# d1-stepper-shield.net
KiCad netlist of a schematic drawn in EAGLE
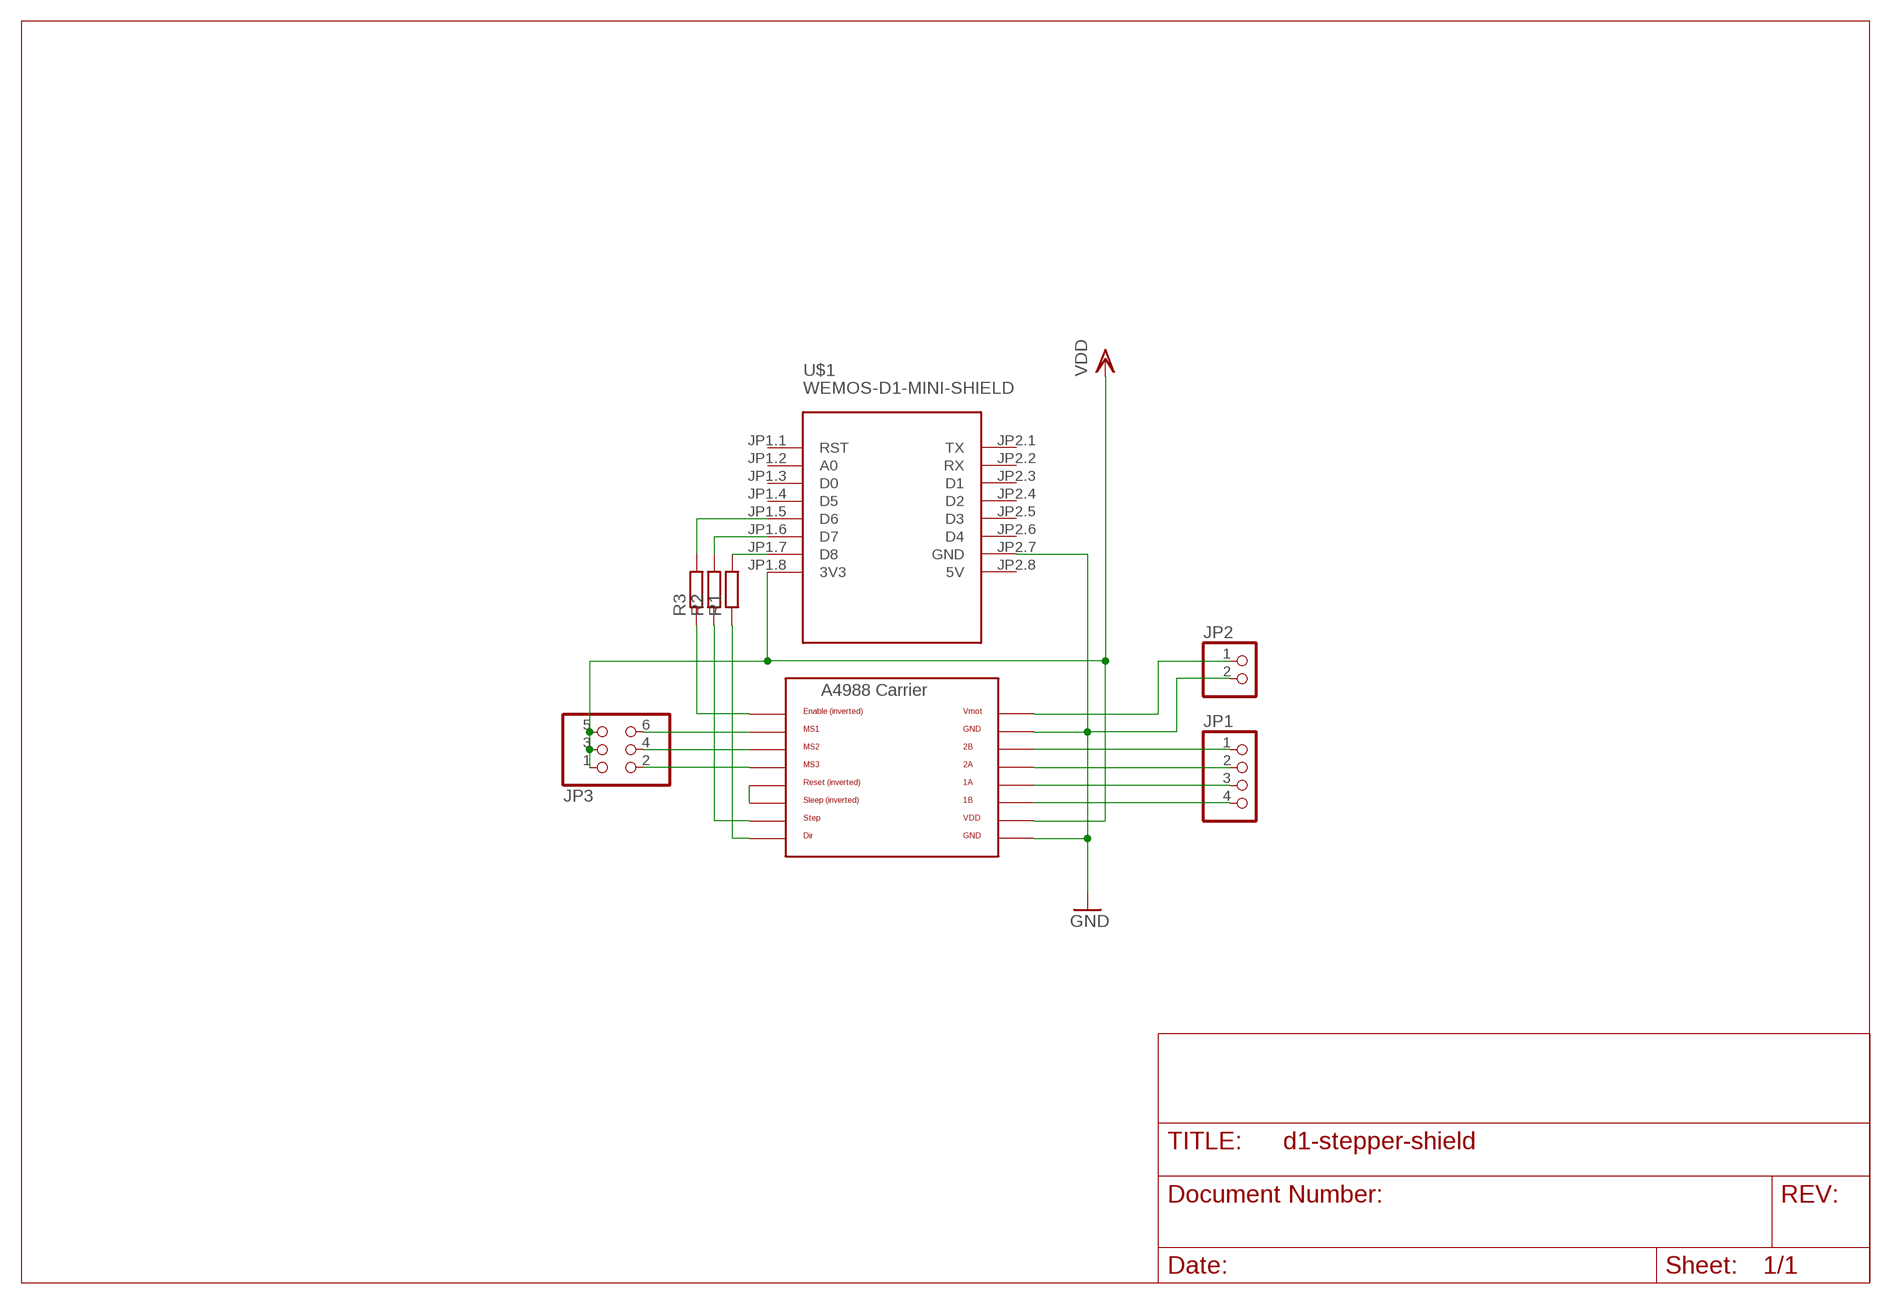
[diagram p0: schematic, sheet 1]

(export (version "E")
  (design (tool "Eeschema 10.0.6"))
  (components
    (comp (ref "JP1")
      (value "PINHD-1X4")
      (footprint "eagle-import:1X04")
      (libsource (lib "eagle-import") (part "PINHD-1X4"))
    )
    (comp (ref "JP2")
      (value "PINHD-1X2")
      (footprint "eagle-import:1X02")
      (libsource (lib "eagle-import") (part "PINHD-1X2"))
    )
    (comp (ref "JP3")
      (value "PINHD-2X3")
      (footprint "eagle-import:2X03")
      (libsource (lib "eagle-import") (part "PINHD-2X3"))
    )
    (comp (ref "R1")
      (value "R-EU_R0603")
      (footprint "eagle-import:R0603")
      (libsource (lib "eagle-import") (part "R-EU_R0603"))
    )
    (comp (ref "R2")
      (value "R-EU_R0603")
      (footprint "eagle-import:R0603")
      (libsource (lib "eagle-import") (part "R-EU_R0603"))
    )
    (comp (ref "R3")
      (value "R-EU_R0603")
      (footprint "eagle-import:R0603")
      (libsource (lib "eagle-import") (part "R-EU_R0603"))
    )
    (comp (ref "U$1")
      (value "WEMOS-D1-MINI-SHIELD")
      (footprint "eagle-import:WEMOS-D1-MINI-SHIELD")
      (libsource (lib "eagle-import") (part "WEMOS-D1-MINI-SHIELD"))
    )
    (comp (ref "U$2")
      (value "A4988BREAKOUT")
      (footprint "eagle-import:A4988BREAKOUT")
      (libsource (lib "eagle-import") (part "A4988BREAKOUT"))
    )
  )
  (nets
    (net (code "1") (name "/5V") (class "Default")
      (node (ref "U$1") (pin "JP2.8") (pinfunction "5V_JP2.8") (pintype "power_in"))
    )
    (net (code "2") (name "GND") (class "Default")
      (node (ref "JP2") (pin "2") (pinfunction "2_2") (pintype "passive"))
      (node (ref "U$1") (pin "JP2.7") (pinfunction "GND_JP2.7") (pintype "power_in"))
      (node (ref "U$2") (pin "GND") (pinfunction "GND_GND") (pintype "power_in"))
      (node (ref "U$2") (pin "GND@0") (pinfunction "GND_GND@0") (pintype "power_in"))
    )
    (net (code "3") (name "Net-(JP1-Pad1)") (class "Default")
      (node (ref "JP1") (pin "1") (pinfunction "1_1") (pintype "passive"))
      (node (ref "U$2") (pin "2B") (pinfunction "2B_2B") (pintype "output"))
    )
    (net (code "4") (name "Net-(JP1-Pad2)") (class "Default")
      (node (ref "JP1") (pin "2") (pinfunction "2_2") (pintype "passive"))
      (node (ref "U$2") (pin "2A") (pinfunction "2A_2A") (pintype "output"))
    )
    (net (code "5") (name "Net-(JP1-Pad3)") (class "Default")
      (node (ref "JP1") (pin "3") (pinfunction "3_3") (pintype "passive"))
      (node (ref "U$2") (pin "1A") (pinfunction "1A_1A") (pintype "output"))
    )
    (net (code "6") (name "Net-(JP1-Pad4)") (class "Default")
      (node (ref "JP1") (pin "4") (pinfunction "4_4") (pintype "passive"))
      (node (ref "U$2") (pin "1B") (pinfunction "1B_1B") (pintype "output"))
    )
    (net (code "7") (name "Net-(JP2-Pad1)") (class "Default")
      (node (ref "JP2") (pin "1") (pinfunction "1_1") (pintype "passive"))
      (node (ref "U$2") (pin "VMOT") (pinfunction "VMOT_VMOT") (pintype "power_in"))
    )
    (net (code "8") (name "Net-(JP3-Pad2)") (class "Default")
      (node (ref "JP3") (pin "2") (pinfunction "2_2") (pintype "passive"))
      (node (ref "U$2") (pin "MS3") (pinfunction "MS3_MS3") (pintype "input"))
    )
    (net (code "9") (name "Net-(JP3-Pad4)") (class "Default")
      (node (ref "JP3") (pin "4") (pinfunction "4_4") (pintype "passive"))
      (node (ref "U$2") (pin "MS2") (pinfunction "MS2_MS2") (pintype "input"))
    )
    (net (code "10") (name "Net-(JP3-Pad6)") (class "Default")
      (node (ref "JP3") (pin "6") (pinfunction "6_6") (pintype "passive"))
      (node (ref "U$2") (pin "MS1") (pinfunction "MS1_MS1") (pintype "input"))
    )
    (net (code "11") (name "Net-(R1-Pad1)") (class "Default")
      (node (ref "R1") (pin "1") (pinfunction "1_1") (pintype "passive"))
      (node (ref "U$2") (pin "DIR") (pinfunction "DIR_DIR") (pintype "input"))
    )
    (net (code "12") (name "Net-(R2-Pad1)") (class "Default")
      (node (ref "R2") (pin "1") (pinfunction "1_1") (pintype "passive"))
      (node (ref "U$2") (pin "STEP") (pinfunction "STEP_STEP") (pintype "input"))
    )
    (net (code "13") (name "Net-(R3-Pad1)") (class "Default")
      (node (ref "R3") (pin "1") (pinfunction "1_1") (pintype "passive"))
      (node (ref "U$2") (pin "EN") (pinfunction "EN_EN") (pintype "input"))
    )
    (net (code "14") (name "Net-(U$1-D6)") (class "Default")
      (node (ref "R3") (pin "2") (pinfunction "2_2") (pintype "passive"))
      (node (ref "U$1") (pin "JP1.5") (pinfunction "D6_JP1.5") (pintype "bidirectional"))
    )
    (net (code "15") (name "Net-(U$1-D7)") (class "Default")
      (node (ref "R2") (pin "2") (pinfunction "2_2") (pintype "passive"))
      (node (ref "U$1") (pin "JP1.6") (pinfunction "D7_JP1.6") (pintype "bidirectional"))
    )
    (net (code "16") (name "Net-(U$1-D8)") (class "Default")
      (node (ref "R1") (pin "2") (pinfunction "2_2") (pintype "passive"))
      (node (ref "U$1") (pin "JP1.7") (pinfunction "D8_JP1.7") (pintype "bidirectional"))
    )
    (net (code "17") (name "Net-(U$2-SLEEP)") (class "Default")
      (node (ref "U$2") (pin "RST") (pinfunction "RST_RST") (pintype "input"))
      (node (ref "U$2") (pin "SLP") (pinfunction "SLEEP_SLP") (pintype "input"))
    )
    (net (code "18") (name "VDD") (class "Default")
      (node (ref "JP3") (pin "1") (pinfunction "1_1") (pintype "passive"))
      (node (ref "JP3") (pin "3") (pinfunction "3_3") (pintype "passive"))
      (node (ref "JP3") (pin "5") (pinfunction "5_5") (pintype "passive"))
      (node (ref "U$1") (pin "JP1.8") (pinfunction "3V3_JP1.8") (pintype "power_in"))
      (node (ref "U$2") (pin "VDD") (pinfunction "VDD_VDD") (pintype "power_in"))
    )
    (net (code "19") (name "unconnected-(U$1-A0-PadJP1.2)") (class "Default")
      (node (ref "U$1") (pin "JP1.2") (pinfunction "A0_JP1.2") (pintype "bidirectional"))
    )
    (net (code "20") (name "unconnected-(U$1-D0-PadJP1.3)") (class "Default")
      (node (ref "U$1") (pin "JP1.3") (pinfunction "D0_JP1.3") (pintype "bidirectional"))
    )
    (net (code "21") (name "unconnected-(U$1-D1-PadJP2.3)") (class "Default")
      (node (ref "U$1") (pin "JP2.3") (pinfunction "D1_JP2.3") (pintype "bidirectional"))
    )
    (net (code "22") (name "unconnected-(U$1-D2-PadJP2.4)") (class "Default")
      (node (ref "U$1") (pin "JP2.4") (pinfunction "D2_JP2.4") (pintype "bidirectional"))
    )
    (net (code "23") (name "unconnected-(U$1-D3-PadJP2.5)") (class "Default")
      (node (ref "U$1") (pin "JP2.5") (pinfunction "D3_JP2.5") (pintype "bidirectional"))
    )
    (net (code "24") (name "unconnected-(U$1-D4-PadJP2.6)") (class "Default")
      (node (ref "U$1") (pin "JP2.6") (pinfunction "D4_JP2.6") (pintype "bidirectional"))
    )
    (net (code "25") (name "unconnected-(U$1-D5-PadJP1.4)") (class "Default")
      (node (ref "U$1") (pin "JP1.4") (pinfunction "D5_JP1.4") (pintype "bidirectional"))
    )
    (net (code "26") (name "unconnected-(U$1-RST-PadJP1.1)") (class "Default")
      (node (ref "U$1") (pin "JP1.1") (pinfunction "RST_JP1.1") (pintype "bidirectional"))
    )
    (net (code "27") (name "unconnected-(U$1-RX-PadJP2.2)") (class "Default")
      (node (ref "U$1") (pin "JP2.2") (pinfunction "RX_JP2.2") (pintype "bidirectional"))
    )
    (net (code "28") (name "unconnected-(U$1-TX-PadJP2.1)") (class "Default")
      (node (ref "U$1") (pin "JP2.1") (pinfunction "TX_JP2.1") (pintype "bidirectional"))
    )
  )
)
